# PowerIn.net
KiCad netlist of a schematic drawn in Altium Designer
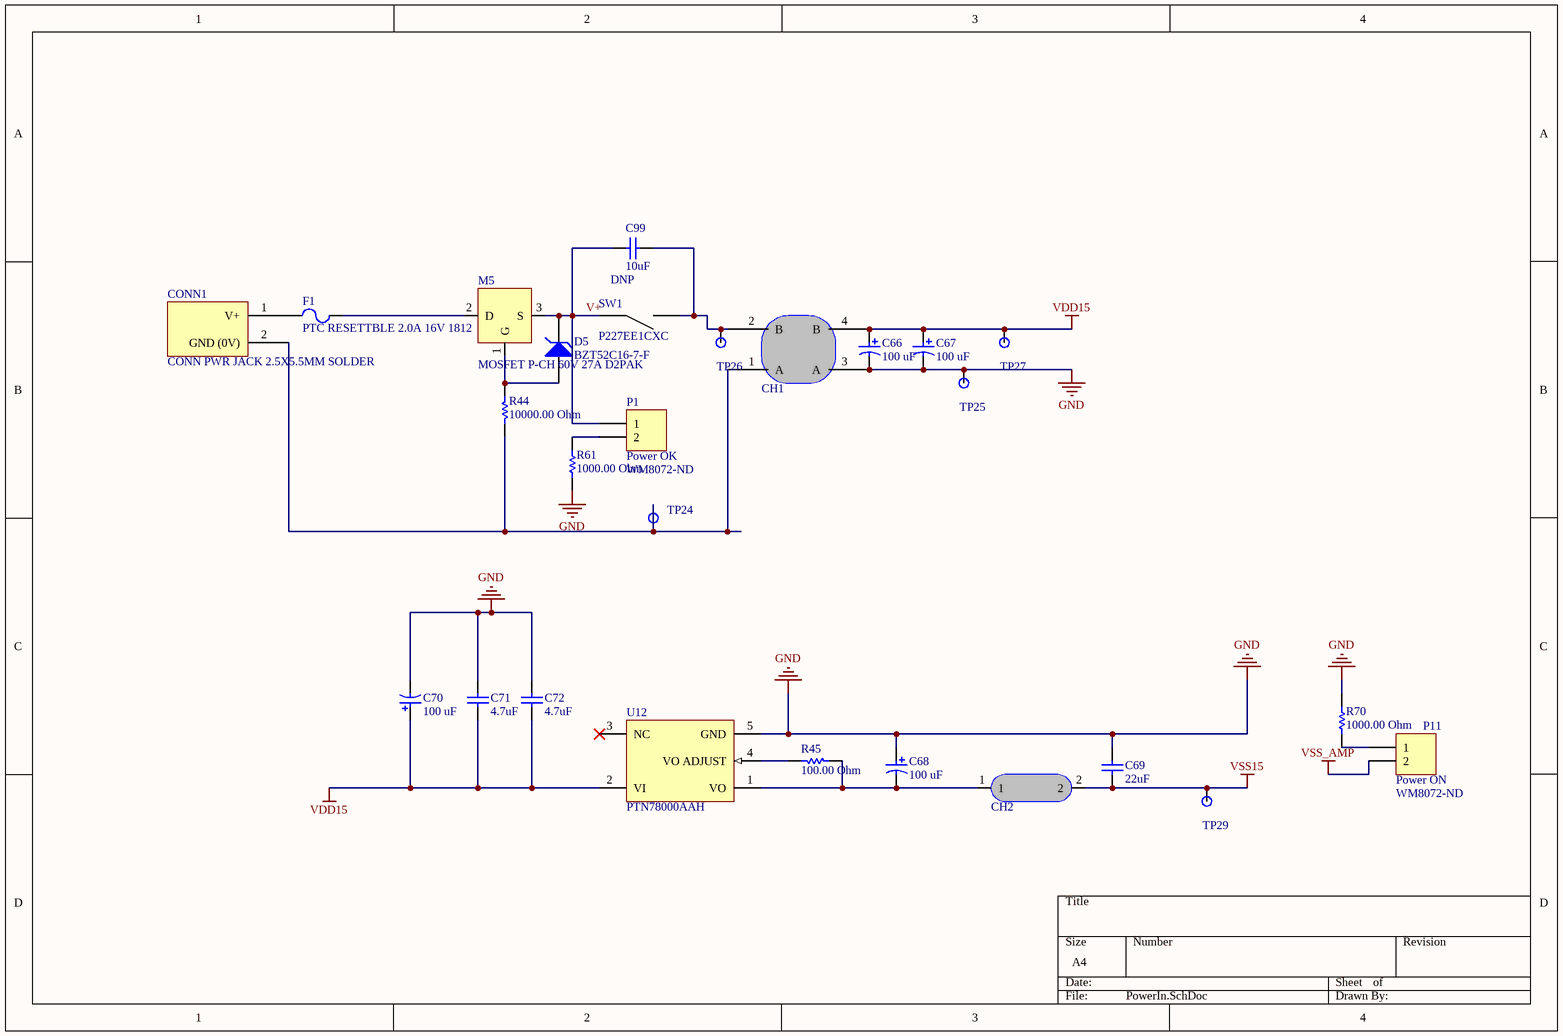
[diagram p0: PowerIn.SchDoc]

(export (version "E")
  (design (tool "Eeschema 10.0.6"))
  (components
    (comp (ref "C66")
      (value "100 uF")
      (footprint "CAPPR55-250-1120X630X1220")
      (fields (field (name "MANUFACTURER") "Panasonic"))
      (libsource (lib "Altium Content Vault") (part "CMP-1665-00015-4"))
    )
    (comp (ref "C67")
      (value "100 uF")
      (footprint "CAPPR55-250-1120X630X1220")
      (fields (field (name "MANUFACTURER") "Panasonic"))
      (libsource (lib "Altium Content Vault") (part "CMP-1665-00015-4"))
    )
    (comp (ref "C68")
      (value "100 uF")
      (footprint "CAPPR55-250-1120X630X1220")
      (fields (field (name "MANUFACTURER") "Panasonic"))
      (libsource (lib "Altium Content Vault") (part "CMP-1665-00015-4"))
    )
    (comp (ref "C69")
      (value "22uF")
      (footprint "CAPC1206(3216)190_M")
      (description "CAP 22uF 25V ±20% 1206 (3216 Metric) Thickness 1.9mm SMD")
      (fields (field (name "TOLERANCE") "Â±20%") (field (name "Comment") "CAP 22uF 25V 1206(3216)"))
      (libsource (lib "Altium Content Vault") (part "CMP-1037-04995-1"))
    )
    (comp (ref "C70")
      (value "100 uF")
      (footprint "CAPPR55-250-1120X630X1220")
      (fields (field (name "MANUFACTURER") "Panasonic"))
      (libsource (lib "Altium Content Vault") (part "CMP-1665-00015-4"))
    )
    (comp (ref "C71")
      (value "4.7uF")
      (footprint "CAPC0805(2012)145_L")
      (description "CAP 4.7uF 25V ±10% 0805 (2012 Metric) Thickness 1.45mm SMD")
      (fields (field (name "TOLERANCE") "Â±10%") (field (name "Comment") "CAP 4.7uF 25V 0805(2012)"))
      (libsource (lib "Altium Content Vault") (part "CMP-1036-04895-1"))
    )
    (comp (ref "C72")
      (value "4.7uF")
      (footprint "CAPC0805(2012)145_L")
      (description "CAP 4.7uF 25V ±10% 0805 (2012 Metric) Thickness 1.45mm SMD")
      (fields (field (name "TOLERANCE") "Â±10%") (field (name "Comment") "CAP 4.7uF 25V 0805(2012)"))
      (libsource (lib "Altium Content Vault") (part "CMP-1036-04895-1"))
    )
    (comp (ref "C99")
      (value "10uF")
      (footprint "CAPC1206(3216)190_L")
      (description "CAP 10uF 25V ±10% 1206 (3216 Metric) Thickness 1.9mm SMD")
      (fields
        (field (name "TOLERANCE") "Â±10%")
        (field (name "OPTION") "DNP")
        (field (name "Comment") "CAP 10uF 25V 1206(3216)")
      )
      (libsource (lib "Altium Content Vault") (part "CMP-1037-04979-1"))
    )
    (comp (ref "CH1")
      (value "10uH 2.4A COMMON CHOKE")
      (footprint "10uH 2.4A COMMON CHOKE")
      (description "CMC 10UH 2.25A 2LN 9 KOHM SMD")
      (fields
        (field (name "MANUFACTURER") "Wurth Electronics Inc.")
        (field (name "MANUFACTURER PART NUMBER") "744282100")
        (field (name "PUBLISHER") "Altium Limited")
      )
      (libsource (lib "AnserEMT") (part "10uH 2.4A COMMON CHOKE"))
    )
    (comp (ref "CH2")
      (value "FIXED IND 10UH 5A 25 MOHM SMD")
      (footprint "FIXED IND 10UH 5A 190 MOHM SMD")
      (fields
        (field (name "MANUFACTURER") "Wurth Electronics Inc.")
        (field (name "MANUFACTURER PART NUMBER") "74477110")
        (field (name "TOLERANCE") "±20%")
        (field (name "PUBLISHER") "Altium Limited")
      )
      (libsource (lib "AnserEMT") (part "74477110"))
    )
    (comp (ref "CONN1")
      (value "CONN PWR JACK 2.5X5.5MM SOLDER")
      (footprint "CONN PWR JACK 2.5X5.5MM SOLDER")
      (fields
        (field (name "MANUFACTURER") "Switchcraft Inc.")
        (field (name "MANUFACTURER PART NUMBER") "RAPC712X")
        (field (name "PUBLISHER") "Altium Limited")
      )
      (libsource (lib "AnserEMT") (part "RAPC712X"))
    )
    (comp (ref "D5")
      (value "BZT52C16-7-F")
      (footprint "DIOD-SOD123-2_V")
      (description "Surface Mount Zener Diode, 16 V, -65 to 125 degC, SOD123, RoHS, Tape and Reel")
      (fields (field (name "MANUFACTURER") "Diodes Inc"))
      (libsource (lib "Altium Content Vault") (part "CMP-0860-00001-1"))
    )
    (comp (ref "F1")
      (value "PTC RESETTBLE 2.0A 16V 1812")
      (footprint "TC RESETTBLE 2.0A 16V 1812")
      (fields
        (field (name "MANUFACTURER") "Bel Fuse Inc.")
        (field (name "MANUFACTURER PART NUMBER") "0ZCG0200AF2B")
        (field (name "PUBLISHER") "Altium Limited")
      )
      (libsource (lib "AnserEMT") (part "TC RESETTBLE 2.0A 16V 1812"))
    )
    (comp (ref "M5")
      (value "MOSFET P-CH 60V 27A D2PAK")
      (footprint "DPAK228P1525X483-3N")
      (fields
        (field (name "MANUFACTURER") "Fairchild/ON Semiconductor")
        (field (name "MANUFACTURER PART NUMBER") "FQB27P06TM")
        (field (name "PUBLISHER") "Altium Limited")
      )
      (libsource (lib "AnserEMT") (part "MOSFET P-CH 60V 27A D2PAK"))
    )
    (comp (ref "P1")
      (value "Power OK")
      (footprint "HDR1X2")
      (description "Header, 2-Pin")
      (fields
        (field (name "SUPPLIER PART NUMBER 1") "WM8072-ND")
        (field (name "MANUFACTURER") "Molex, LLC")
        (field (name "MANUFACTURER PART NUMBER") "0901200122")
        (field (name "PUBLISHER") "Altium Limited")
      )
      (libsource (lib "Miscellaneous Connectors") (part "Header 2"))
    )
    (comp (ref "P11")
      (value "Power ON")
      (footprint "HDR1X2")
      (description "Header, 2-Pin")
      (fields
        (field (name "SUPPLIER PART NUMBER 1") "WM8072-ND")
        (field (name "MANUFACTURER") "Molex, LLC")
        (field (name "MANUFACTURER PART NUMBER") "0901200122")
        (field (name "PUBLISHER") "Altium Limited")
      )
      (libsource (lib "Miscellaneous Connectors") (part "Header 2"))
    )
    (comp (ref "R44")
      (value "10000.00 Ohm")
      (footprint "RESC0603(1608)_N")
      (description "10K 0.1W 5% 0603 (1608 Metric)  SMD")
      (fields (field (name "TOLERANCE") "5 %") (field (name "POWER") "0.1 W"))
      (libsource (lib "Altium Content Vault") (part "CMP-1012-00098-1"))
    )
    (comp (ref "R45")
      (value "100.00 Ohm")
      (footprint "RESC0603(1608)_M")
      (description "100R 0.1W 1% 0603 (1608 Metric)  SMD")
      (fields (field (name "TOLERANCE") "1 %") (field (name "POWER") "0.1 W"))
      (libsource (lib "Altium Content Vault") (part "CMP-1012-00397-1"))
    )
    (comp (ref "R61")
      (value "1000.00 Ohm")
      (footprint "RESC0603(1608)_L")
      (description "1K 0.1W 5% 0603 (1608 Metric)  SMD")
      (fields (field (name "TOLERANCE") "5 %") (field (name "POWER") "0.1 W"))
      (libsource (lib "Altium Content Vault") (part "CMP-1012-00074-1"))
    )
    (comp (ref "R70")
      (value "1000.00 Ohm")
      (footprint "RESC0603(1608)_L")
      (description "1K 0.1W 5% 0603 (1608 Metric)  SMD")
      (fields (field (name "TOLERANCE") "5 %") (field (name "POWER") "0.1 W"))
      (libsource (lib "Altium Content Vault") (part "CMP-1012-00074-1"))
    )
    (comp (ref "SW1")
      (value "P227EE1CXC")
      (footprint "P227EE1CXC")
      (description "SWITCH PUSHBUTTON DPST 7A 125V")
      (fields (field (name "MANUFACTURER") "E-Switch") (field (name "PUBLISHER") "Altium Limited"))
      (libsource (lib "AnserEMT") (part "P227EE1CXC"))
    )
    (comp (ref "TP24")
      (value "Testpoint")
      (footprint "0603 PROBE PAD")
      (description "0.063\" x 0.031\" x 0.045\" (1.60mm x 0.80mm x 1.15mm)")
      (libsource (lib "testpoint") (part "Testpoint"))
    )
    (comp (ref "TP25")
      (value "Testpoint")
      (footprint "0603 PROBE PAD")
      (description "0.063\" x 0.031\" x 0.045\" (1.60mm x 0.80mm x 1.15mm)")
      (libsource (lib "testpoint") (part "Testpoint"))
    )
    (comp (ref "TP26")
      (value "Testpoint")
      (footprint "0603 PROBE PAD")
      (description "0.063\" x 0.031\" x 0.045\" (1.60mm x 0.80mm x 1.15mm)")
      (libsource (lib "testpoint") (part "Testpoint"))
    )
    (comp (ref "TP27")
      (value "Testpoint")
      (footprint "0603 PROBE PAD")
      (description "0.063\" x 0.031\" x 0.045\" (1.60mm x 0.80mm x 1.15mm)")
      (libsource (lib "testpoint") (part "Testpoint"))
    )
    (comp (ref "TP29")
      (value "Testpoint")
      (footprint "0603 PROBE PAD")
      (description "0.063\" x 0.031\" x 0.045\" (1.60mm x 0.80mm x 1.15mm)")
      (libsource (lib "testpoint") (part "Testpoint"))
    )
    (comp (ref "U12")
      (value "PTN78000AAH")
      (footprint "EUS0005A")
      (fields (field (name "MANUFACTURER") "Texas Instruments"))
      (libsource (lib "Altium Content Vault") (part "CMP-0387-00611-2"))
    )
  )
  (nets
    (net (code "1") (name "/V+") (class "Default")
      (node (ref "C99") (pin "2") (pinfunction "2_2") (pintype "passive"))
      (node (ref "D5") (pin "2") (pinfunction "K_2") (pintype "passive"))
      (node (ref "M5") (pin "3") (pinfunction "S_3") (pintype "passive"))
      (node (ref "P1") (pin "1") (pinfunction "1_1") (pintype "passive"))
      (node (ref "SW1") (pin "1") (pinfunction "1_1") (pintype "passive"))
    )
    (net (code "2") (name "GND") (class "Default")
      (node (ref "C66") (pin "2") (pinfunction "2_2") (pintype "passive"))
      (node (ref "C67") (pin "2") (pinfunction "2_2") (pintype "passive"))
      (node (ref "C68") (pin "1") (pinfunction "1_1") (pintype "passive"))
      (node (ref "C69") (pin "2") (pinfunction "2_2") (pintype "passive"))
      (node (ref "C70") (pin "2") (pinfunction "2_2") (pintype "passive"))
      (node (ref "C71") (pin "1") (pinfunction "1_1") (pintype "passive"))
      (node (ref "C72") (pin "1") (pinfunction "1_1") (pintype "passive"))
      (node (ref "CH1") (pin "3") (pinfunction "A_3") (pintype "passive"))
      (node (ref "R61") (pin "2") (pinfunction "2_2") (pintype "passive"))
      (node (ref "R70") (pin "1") (pinfunction "1_1") (pintype "passive"))
      (node (ref "TP25") (pin "0") (pintype "passive"))
      (node (ref "U12") (pin "5") (pinfunction "GND_5") (pintype "power_in"))
    )
    (net (code "3") (name "Net-(C99-Pad1)") (class "Default")
      (node (ref "C99") (pin "1") (pinfunction "1_1") (pintype "passive"))
      (node (ref "CH1") (pin "2") (pinfunction "B_2") (pintype "passive"))
      (node (ref "SW1") (pin "2") (pinfunction "2_2") (pintype "passive"))
      (node (ref "TP26") (pin "0") (pintype "passive"))
    )
    (net (code "4") (name "Net-(CONN1-GND_(0V))") (class "Default")
      (node (ref "CH1") (pin "1") (pinfunction "A_1") (pintype "passive"))
      (node (ref "CONN1") (pin "2") (pinfunction "GND_(0V)_2") (pintype "passive"))
      (node (ref "R44") (pin "1") (pinfunction "1_1") (pintype "passive"))
      (node (ref "TP24") (pin "0") (pintype "passive"))
    )
    (net (code "5") (name "Net-(CONN1-V+)") (class "Default")
      (node (ref "CONN1") (pin "1") (pinfunction "V+_1") (pintype "passive"))
      (node (ref "F1") (pin "1") (pinfunction "1_1") (pintype "passive"))
    )
    (net (code "6") (name "Net-(D5-A)") (class "Default")
      (node (ref "D5") (pin "1") (pinfunction "A_1") (pintype "passive"))
      (node (ref "M5") (pin "1") (pinfunction "G_1") (pintype "passive"))
      (node (ref "R44") (pin "2") (pinfunction "2_2") (pintype "passive"))
    )
    (net (code "7") (name "Net-(M5-D)") (class "Default")
      (node (ref "F1") (pin "2") (pinfunction "2_2") (pintype "passive"))
      (node (ref "M5") (pin "2") (pinfunction "D_2") (pintype "passive"))
    )
    (net (code "8") (name "Net-(P1-Pad2)") (class "Default")
      (node (ref "P1") (pin "2") (pinfunction "2_2") (pintype "passive"))
      (node (ref "R61") (pin "1") (pinfunction "1_1") (pintype "passive"))
    )
    (net (code "9") (name "Net-(P11-Pad1)") (class "Default")
      (node (ref "P11") (pin "1") (pinfunction "1_1") (pintype "passive"))
      (node (ref "R70") (pin "2") (pinfunction "2_2") (pintype "passive"))
    )
    (net (code "10") (name "Net-(U12-VO)") (class "Default")
      (node (ref "C68") (pin "2") (pinfunction "2_2") (pintype "passive"))
      (node (ref "CH2") (pin "1") (pinfunction "1_1") (pintype "passive"))
      (node (ref "R45") (pin "1") (pinfunction "1_1") (pintype "passive"))
      (node (ref "U12") (pin "1") (pinfunction "VO_1") (pintype "power_in"))
    )
    (net (code "11") (name "Net-(U12-VO_ADJUST)") (class "Default")
      (node (ref "R45") (pin "2") (pinfunction "2_2") (pintype "passive"))
      (node (ref "U12") (pin "4") (pinfunction "VO_ADJUST_4") (pintype "input"))
    )
    (net (code "12") (name "VDD15") (class "Default")
      (node (ref "C66") (pin "1") (pinfunction "1_1") (pintype "passive"))
      (node (ref "C67") (pin "1") (pinfunction "1_1") (pintype "passive"))
      (node (ref "C70") (pin "1") (pinfunction "1_1") (pintype "passive"))
      (node (ref "C71") (pin "2") (pinfunction "2_2") (pintype "passive"))
      (node (ref "C72") (pin "2") (pinfunction "2_2") (pintype "passive"))
      (node (ref "CH1") (pin "4") (pinfunction "B_4") (pintype "passive"))
      (node (ref "TP27") (pin "0") (pintype "passive"))
      (node (ref "U12") (pin "2") (pinfunction "VI_2") (pintype "power_in"))
    )
    (net (code "13") (name "VSS15") (class "Default")
      (node (ref "C69") (pin "1") (pinfunction "1_1") (pintype "passive"))
      (node (ref "CH2") (pin "2") (pinfunction "2_2") (pintype "passive"))
      (node (ref "TP29") (pin "0") (pintype "passive"))
    )
    (net (code "14") (name "VSS_AMP") (class "Default")
      (node (ref "P11") (pin "2") (pinfunction "2_2") (pintype "passive"))
    )
    (net (code "15") (name "unconnected-(U12-NC-Pad3)") (class "Default")
      (node (ref "U12") (pin "3") (pinfunction "NC_3") (pintype "passive+no_connect"))
    )
  )
)
